# Sheet_1.net
KiCad netlist of a schematic drawn in EasyEDA
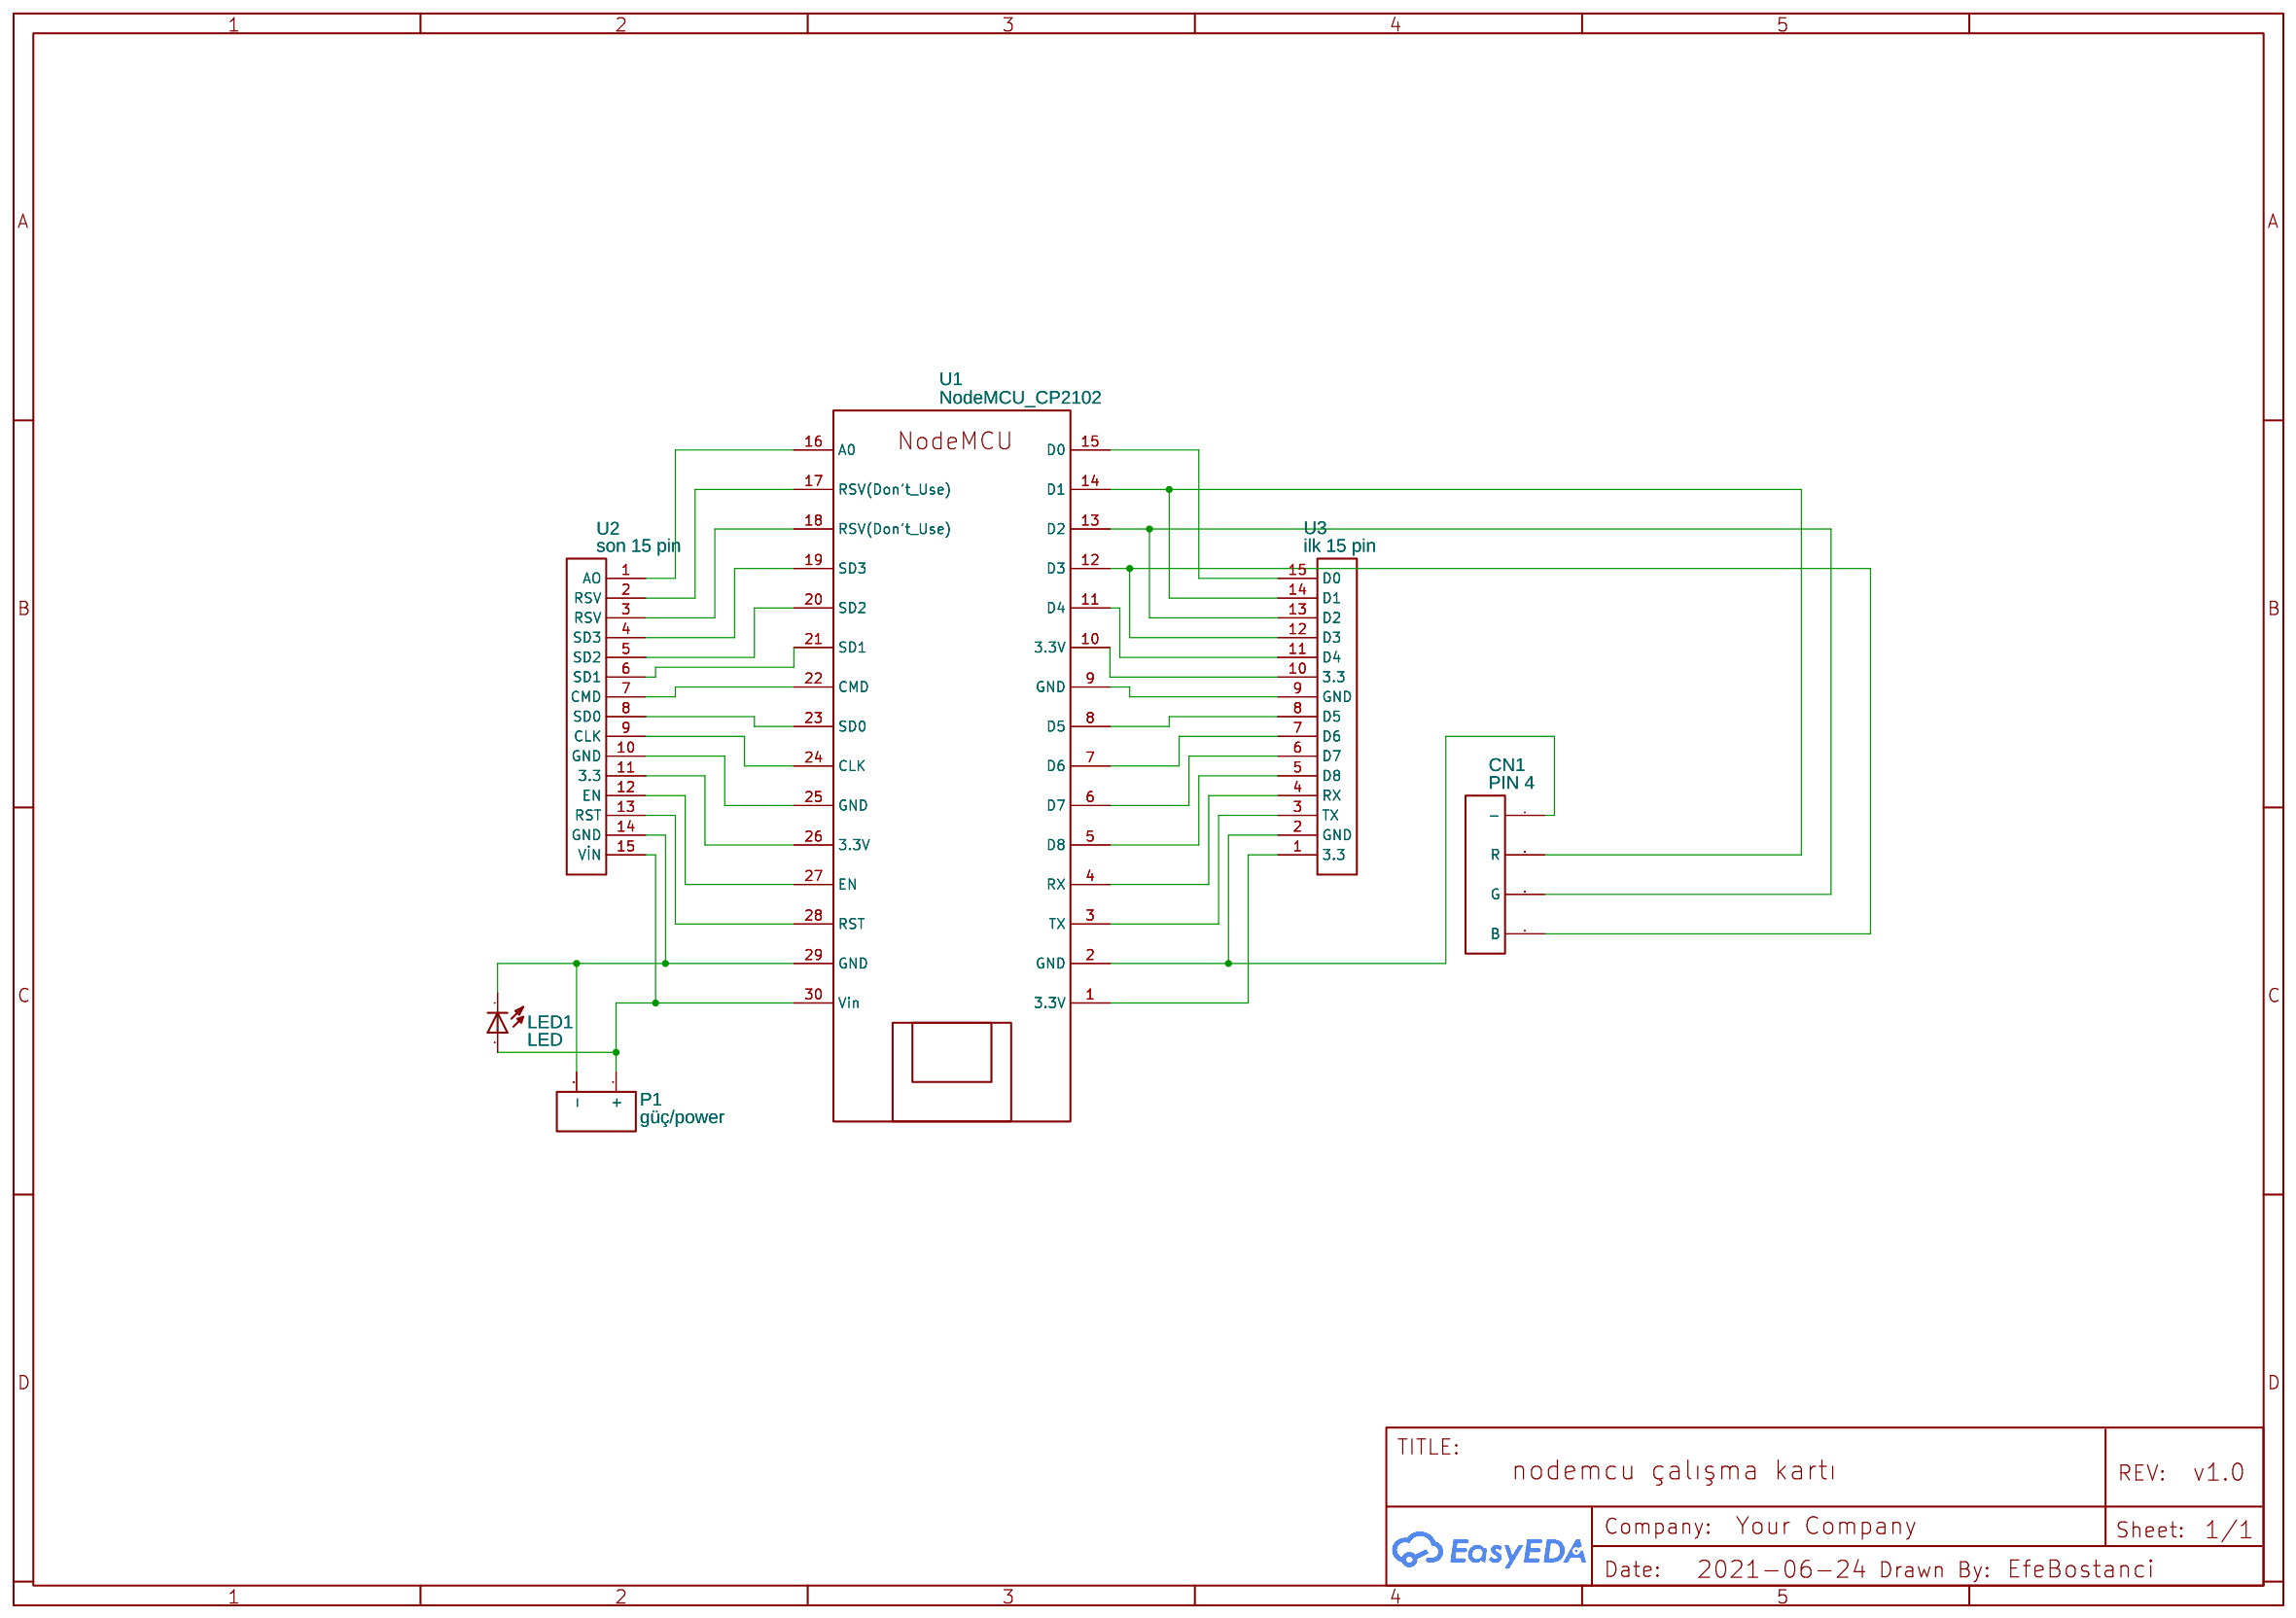
[diagram p0: schematic sheet]

(export (version "E")
  (design (tool "Eeschema 10.0.6"))
  (components
    (comp (ref "CN1") (value "PIN 4") (libsource (lib "") (part "PIN 4")))
    (comp (ref "LED1") (value "LED") (libsource (lib "") (part "LED")))
    (comp (ref "P1")
      (value "güç/power")
      (fields
        (field (name "BOM_Manufacturer Part") "Header-Female-2.54_1x4")
        (field (name "BOM_Supplier Part") "C124413")
      )
      (libsource (lib "") (part "Header_2.54_1x2"))
    )
    (comp (ref "U1") (value "NodeMCU_CP2102") (libsource (lib "") (part "NodeMCU_CP2102")))
    (comp (ref "U2") (value "son 15 pin") (libsource (lib "") (part "15 pin_1")))
    (comp (ref "U3") (value "ilk 15 pin") (libsource (lib "") (part "15 pin")))
  )
  (nets
    (net (code "1") (name "Net-(CN1--)") (class "Default")
      (node (ref "CN1") (pin "4") (pinfunction "-_4") (pintype "bidirectional"))
      (node (ref "U1") (pin "2") (pinfunction "GND_2") (pintype "unspecified"))
      (node (ref "U3") (pin "2") (pinfunction "GND_2") (pintype "unspecified"))
    )
    (net (code "2") (name "Net-(CN1-B)") (class "Default")
      (node (ref "CN1") (pin "1") (pinfunction "B_1") (pintype "bidirectional"))
      (node (ref "U1") (pin "12") (pinfunction "D3_12") (pintype "unspecified"))
      (node (ref "U3") (pin "12") (pinfunction "D3_12") (pintype "unspecified"))
    )
    (net (code "3") (name "Net-(CN1-G)") (class "Default")
      (node (ref "CN1") (pin "2") (pinfunction "G_2") (pintype "bidirectional"))
      (node (ref "U1") (pin "13") (pinfunction "D2_13") (pintype "unspecified"))
      (node (ref "U3") (pin "13") (pinfunction "D2_13") (pintype "unspecified"))
    )
    (net (code "4") (name "Net-(CN1-R)") (class "Default")
      (node (ref "CN1") (pin "3") (pinfunction "R_3") (pintype "bidirectional"))
      (node (ref "U1") (pin "14") (pinfunction "D1_14") (pintype "unspecified"))
      (node (ref "U3") (pin "14") (pinfunction "D1_14") (pintype "unspecified"))
    )
    (net (code "5") (name "Net-(LED1-C)") (class "Default")
      (node (ref "LED1") (pin "K") (pinfunction "C_K") (pintype "unspecified"))
      (node (ref "P1") (pin "2") (pinfunction "-_2") (pintype "input"))
      (node (ref "U1") (pin "29") (pinfunction "GND_29") (pintype "unspecified"))
      (node (ref "U2") (pin "14") (pinfunction "GND_14") (pintype "unspecified"))
    )
    (net (code "6") (name "Net-(P1-+)") (class "Default")
      (node (ref "LED1") (pin "A") (pinfunction "A_A") (pintype "unspecified"))
      (node (ref "P1") (pin "1") (pinfunction "+_1") (pintype "input"))
      (node (ref "U1") (pin "30") (pinfunction "Vin_30") (pintype "unspecified"))
      (node (ref "U2") (pin "15") (pinfunction "VİN_15") (pintype "unspecified"))
    )
    (net (code "7") (name "Net-(U1-3.3V-Pad1)") (class "Default")
      (node (ref "U1") (pin "1") (pinfunction "3.3V_1") (pintype "unspecified"))
      (node (ref "U3") (pin "1") (pinfunction "3.3_1") (pintype "unspecified"))
    )
    (net (code "8") (name "Net-(U1-3.3V-Pad10)") (class "Default")
      (node (ref "U1") (pin "10") (pinfunction "3.3V_10") (pintype "unspecified"))
      (node (ref "U3") (pin "10") (pinfunction "3.3_10") (pintype "unspecified"))
    )
    (net (code "9") (name "Net-(U1-A0)") (class "Default")
      (node (ref "U1") (pin "16") (pinfunction "A0_16") (pintype "unspecified"))
      (node (ref "U2") (pin "1") (pinfunction "AO_1") (pintype "unspecified"))
    )
    (net (code "10") (name "Net-(U1-CLK)") (class "Default")
      (node (ref "U1") (pin "24") (pinfunction "CLK_24") (pintype "unspecified"))
      (node (ref "U2") (pin "9") (pinfunction "CLK_9") (pintype "unspecified"))
    )
    (net (code "11") (name "Net-(U1-CMD)") (class "Default")
      (node (ref "U1") (pin "22") (pinfunction "CMD_22") (pintype "unspecified"))
      (node (ref "U2") (pin "7") (pinfunction "CMD_7") (pintype "unspecified"))
    )
    (net (code "12") (name "Net-(U1-D0)") (class "Default")
      (node (ref "U1") (pin "15") (pinfunction "D0_15") (pintype "unspecified"))
      (node (ref "U3") (pin "15") (pinfunction "D0_15") (pintype "unspecified"))
    )
    (net (code "13") (name "Net-(U1-D4)") (class "Default")
      (node (ref "U1") (pin "11") (pinfunction "D4_11") (pintype "unspecified"))
      (node (ref "U3") (pin "11") (pinfunction "D4_11") (pintype "unspecified"))
    )
    (net (code "14") (name "Net-(U1-D5)") (class "Default")
      (node (ref "U1") (pin "8") (pinfunction "D5_8") (pintype "unspecified"))
      (node (ref "U3") (pin "8") (pinfunction "D5_8") (pintype "unspecified"))
    )
    (net (code "15") (name "Net-(U1-D6)") (class "Default")
      (node (ref "U1") (pin "7") (pinfunction "D6_7") (pintype "unspecified"))
      (node (ref "U3") (pin "7") (pinfunction "D6_7") (pintype "unspecified"))
    )
    (net (code "16") (name "Net-(U1-D7)") (class "Default")
      (node (ref "U1") (pin "6") (pinfunction "D7_6") (pintype "unspecified"))
      (node (ref "U3") (pin "6") (pinfunction "D7_6") (pintype "unspecified"))
    )
    (net (code "17") (name "Net-(U1-D8)") (class "Default")
      (node (ref "U1") (pin "5") (pinfunction "D8_5") (pintype "unspecified"))
      (node (ref "U3") (pin "5") (pinfunction "D8_5") (pintype "unspecified"))
    )
    (net (code "18") (name "Net-(U1-EN)") (class "Default")
      (node (ref "U1") (pin "27") (pinfunction "EN_27") (pintype "unspecified"))
      (node (ref "U2") (pin "12") (pinfunction "EN_12") (pintype "unspecified"))
    )
    (net (code "19") (name "Net-(U1-GND-Pad9)") (class "Default")
      (node (ref "U1") (pin "9") (pinfunction "GND_9") (pintype "unspecified"))
      (node (ref "U3") (pin "9") (pinfunction "GND_9") (pintype "unspecified"))
    )
    (net (code "20") (name "Net-(U1-GND-Pad25)") (class "Default")
      (node (ref "U1") (pin "25") (pinfunction "GND_25") (pintype "unspecified"))
      (node (ref "U2") (pin "10") (pinfunction "GND_10") (pintype "unspecified"))
    )
    (net (code "21") (name "Net-(U1-RST)") (class "Default")
      (node (ref "U1") (pin "28") (pinfunction "RST_28") (pintype "unspecified"))
      (node (ref "U2") (pin "13") (pinfunction "RST_13") (pintype "unspecified"))
    )
    (net (code "22") (name "Net-(U1-RSV(Don't_Use)-Pad17)") (class "Default")
      (node (ref "U1") (pin "17") (pinfunction "RSV(Don't_Use)_17") (pintype "unspecified"))
      (node (ref "U2") (pin "2") (pinfunction "RSV_2") (pintype "unspecified"))
    )
    (net (code "23") (name "Net-(U1-RSV(Don't_Use)-Pad18)") (class "Default")
      (node (ref "U1") (pin "18") (pinfunction "RSV(Don't_Use)_18") (pintype "unspecified"))
      (node (ref "U2") (pin "3") (pinfunction "RSV_3") (pintype "unspecified"))
    )
    (net (code "24") (name "Net-(U1-RX)") (class "Default")
      (node (ref "U1") (pin "4") (pinfunction "RX_4") (pintype "unspecified"))
      (node (ref "U3") (pin "4") (pinfunction "RX_4") (pintype "unspecified"))
    )
    (net (code "25") (name "Net-(U1-SD0)") (class "Default")
      (node (ref "U1") (pin "23") (pinfunction "SD0_23") (pintype "unspecified"))
      (node (ref "U2") (pin "8") (pinfunction "SD0_8") (pintype "unspecified"))
    )
    (net (code "26") (name "Net-(U1-SD1)") (class "Default")
      (node (ref "U1") (pin "21") (pinfunction "SD1_21") (pintype "unspecified"))
      (node (ref "U2") (pin "6") (pinfunction "SD1_6") (pintype "unspecified"))
    )
    (net (code "27") (name "Net-(U1-SD2)") (class "Default")
      (node (ref "U1") (pin "20") (pinfunction "SD2_20") (pintype "unspecified"))
      (node (ref "U2") (pin "5") (pinfunction "SD2_5") (pintype "unspecified"))
    )
    (net (code "28") (name "Net-(U1-SD3)") (class "Default")
      (node (ref "U1") (pin "19") (pinfunction "SD3_19") (pintype "unspecified"))
      (node (ref "U2") (pin "4") (pinfunction "SD3_4") (pintype "unspecified"))
    )
    (net (code "29") (name "Net-(U1-TX)") (class "Default")
      (node (ref "U1") (pin "3") (pinfunction "TX_3") (pintype "unspecified"))
      (node (ref "U3") (pin "3") (pinfunction "TX_3") (pintype "unspecified"))
    )
    (net (code "30") (name "Net-(U2-3.3)") (class "Default")
      (node (ref "U1") (pin "26") (pinfunction "3.3V_26") (pintype "unspecified"))
      (node (ref "U2") (pin "11") (pinfunction "3.3_11") (pintype "unspecified"))
    )
  )
)
